# Payload.net
KiCad netlist of a schematic drawn in Altium Designer
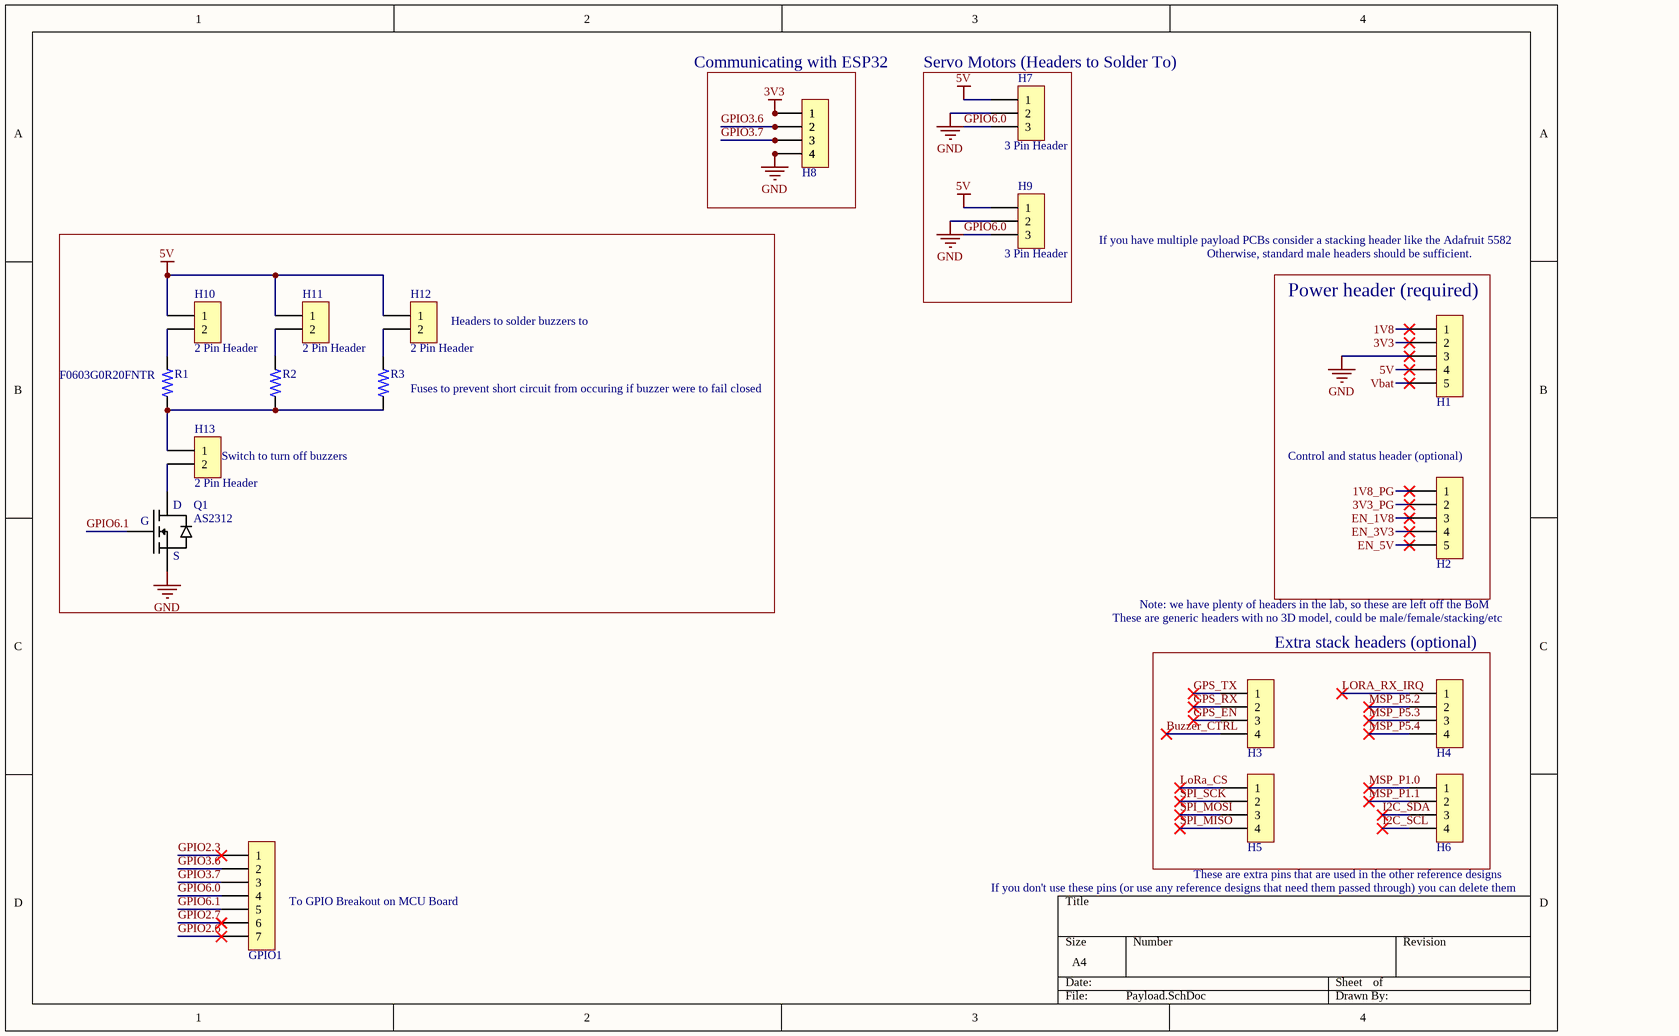
[diagram p0: Payload.SchDoc]

(export (version "E")
  (design (tool "Eeschema 10.0.6"))
  (components
    (comp (ref "GPIO1")
      (value "HDR,2.54mm,1x7")
      (footprint "APSS Connectors:HEADER_2.54MM_1x7PIN")
      (description "Connector - 2.54mm, 1x7-pin")
      (libsource (lib "APSS Connectors") (part "HDR,2.54mm,1x7"))
    )
    (comp (ref "H1")
      (value "Header - 2.54mm,1x5-pin")
      (footprint "HEADER_2.54MM_1x5PIN")
      (libsource (lib "APSS Generic Components") (part "Header - 2.54mm,1x5-pin"))
    )
    (comp (ref "H2")
      (value "Header - 2.54mm,1x5-pin")
      (footprint "HEADER_2.54MM_1x5PIN")
      (libsource (lib "APSS Generic Components") (part "Header - 2.54mm,1x5-pin"))
    )
    (comp (ref "H3")
      (value "Header - 2.54mm,1x4-pin")
      (footprint "HEADER_2.54MM_1x4PIN")
      (libsource (lib "APSS Generic Components") (part "Header - 2.54mm,1x4-pin"))
    )
    (comp (ref "H4")
      (value "Header - 2.54mm,1x4-pin")
      (footprint "HEADER_2.54MM_1x4PIN")
      (libsource (lib "APSS Generic Components") (part "Header - 2.54mm,1x4-pin"))
    )
    (comp (ref "H5")
      (value "Header - 2.54mm,1x4-pin")
      (footprint "HEADER_2.54MM_1x4PIN")
      (libsource (lib "APSS Generic Components") (part "Header - 2.54mm,1x4-pin"))
    )
    (comp (ref "H6")
      (value "Header - 2.54mm,1x4-pin")
      (footprint "HEADER_2.54MM_1x4PIN")
      (libsource (lib "APSS Generic Components") (part "Header - 2.54mm,1x4-pin"))
    )
    (comp (ref "H7")
      (value "3 Pin Header")
      (footprint "3 Pin Header")
      (libsource (lib "Different Header Pin Numbers") (part "3 Pin Header"))
    )
    (comp (ref "H8")
      (value "Header - 2.54mm,1x4-pin")
      (footprint "HEADER_2.54MM_1x4PIN")
      (libsource (lib "APSS Generic Components") (part "Header - 2.54mm,1x4-pin"))
    )
    (comp (ref "H9")
      (value "3 Pin Header")
      (footprint "3 Pin Header")
      (libsource (lib "Different Header Pin Numbers") (part "3 Pin Header"))
    )
    (comp (ref "H10")
      (value "2 Pin Header")
      (footprint "2 Pin Header")
      (libsource (lib "Different Header Pin Numbers") (part "2 Pin Header"))
    )
    (comp (ref "H11")
      (value "2 Pin Header")
      (footprint "2 Pin Header")
      (libsource (lib "Different Header Pin Numbers") (part "2 Pin Header"))
    )
    (comp (ref "H12")
      (value "2 Pin Header")
      (footprint "2 Pin Header")
      (libsource (lib "Different Header Pin Numbers") (part "2 Pin Header"))
    )
    (comp (ref "H13")
      (value "2 Pin Header")
      (footprint "2 Pin Header")
      (libsource (lib "Different Header Pin Numbers") (part "2 Pin Header"))
    )
    (comp (ref "Q1")
      (value "AS2312")
      (footprint "APSS Prototype Parts:SOT23-3N-1.15mm")
      (description "Transistor - MOSFET, N-Channel AS2312")
      (fields (field (name "POWER") "1.2W") (field (name "APSS STANDARD PART") "APSS Standard"))
      (libsource (lib "APSS Prototype Parts") (part "AS2312"))
    )
    (comp (ref "R1")
      (value "F0603G0R20FNTR")
      (footprint "CAPC1608X90")
      (description "200 mA AC 32 V DC Fuse Board Mount (Cartridge Style Excluded) Surface Mount 0603 (1608 Metric)")
      (fields (field (name "MF") "AVX"))
      (libsource (lib "F0603G0R20FNTR") (part "F0603G0R20FNTR"))
    )
    (comp (ref "R2")
      (value "F0603G0R20FNTR")
      (footprint "CAPC1608X90")
      (description "200 mA AC 32 V DC Fuse Board Mount (Cartridge Style Excluded) Surface Mount 0603 (1608 Metric)")
      (fields (field (name "MF") "AVX"))
      (libsource (lib "F0603G0R20FNTR") (part "F0603G0R20FNTR"))
    )
    (comp (ref "R3")
      (value "F0603G0R20FNTR")
      (footprint "CAPC1608X90")
      (description "200 mA AC 32 V DC Fuse Board Mount (Cartridge Style Excluded) Surface Mount 0603 (1608 Metric)")
      (fields (field (name "MF") "AVX"))
      (libsource (lib "F0603G0R20FNTR") (part "F0603G0R20FNTR"))
    )
  )
  (nets
    (net (code "1") (name "/1V8") (class "Default")
      (node (ref "H1") (pin "1") (pinfunction "1_1") (pintype "passive+no_connect"))
    )
    (net (code "2") (name "/1V8_PG") (class "Default")
      (node (ref "H2") (pin "1") (pinfunction "1_1") (pintype "passive+no_connect"))
    )
    (net (code "3") (name "/3V3_PG") (class "Default")
      (node (ref "H2") (pin "2") (pinfunction "2_2") (pintype "passive+no_connect"))
    )
    (net (code "4") (name "/Buzzer_CTRL") (class "Default")
      (node (ref "H3") (pin "4") (pinfunction "4_4") (pintype "passive+no_connect"))
    )
    (net (code "5") (name "/EN_1V8") (class "Default")
      (node (ref "H2") (pin "3") (pinfunction "3_3") (pintype "passive+no_connect"))
    )
    (net (code "6") (name "/EN_3V3") (class "Default")
      (node (ref "H2") (pin "4") (pinfunction "4_4") (pintype "passive+no_connect"))
    )
    (net (code "7") (name "/EN_5V") (class "Default")
      (node (ref "H2") (pin "5") (pinfunction "5_5") (pintype "passive+no_connect"))
    )
    (net (code "8") (name "/GPIO2.3") (class "Default")
      (node (ref "GPIO1") (pin "1") (pinfunction "1_1") (pintype "passive+no_connect"))
    )
    (net (code "9") (name "/GPIO2.6") (class "Default")
      (node (ref "GPIO1") (pin "7") (pinfunction "7_7") (pintype "passive+no_connect"))
    )
    (net (code "10") (name "/GPIO2.7") (class "Default")
      (node (ref "GPIO1") (pin "6") (pinfunction "6_6") (pintype "passive+no_connect"))
    )
    (net (code "11") (name "/GPIO3.6") (class "Default")
      (node (ref "GPIO1") (pin "2") (pinfunction "2_2") (pintype "passive"))
      (node (ref "H8") (pin "2") (pinfunction "2_2") (pintype "passive"))
    )
    (net (code "12") (name "/GPIO3.7") (class "Default")
      (node (ref "GPIO1") (pin "3") (pinfunction "3_3") (pintype "passive"))
      (node (ref "H8") (pin "3") (pinfunction "3_3") (pintype "passive"))
    )
    (net (code "13") (name "/GPIO6.0") (class "Default")
      (node (ref "GPIO1") (pin "4") (pinfunction "4_4") (pintype "passive"))
      (node (ref "H7") (pin "3") (pinfunction "3_3") (pintype "passive"))
      (node (ref "H9") (pin "3") (pinfunction "3_3") (pintype "passive"))
    )
    (net (code "14") (name "/GPIO6.1") (class "Default")
      (node (ref "GPIO1") (pin "5") (pinfunction "5_5") (pintype "passive"))
      (node (ref "Q1") (pin "1") (pinfunction "G_1") (pintype "passive"))
    )
    (net (code "15") (name "/GPS_EN") (class "Default")
      (node (ref "H3") (pin "3") (pinfunction "3_3") (pintype "passive+no_connect"))
    )
    (net (code "16") (name "/GPS_RX") (class "Default")
      (node (ref "H3") (pin "2") (pinfunction "2_2") (pintype "passive+no_connect"))
    )
    (net (code "17") (name "/GPS_TX") (class "Default")
      (node (ref "H3") (pin "1") (pinfunction "1_1") (pintype "passive+no_connect"))
    )
    (net (code "18") (name "/I2C_SCL") (class "Default")
      (node (ref "H6") (pin "4") (pinfunction "4_4") (pintype "passive+no_connect"))
    )
    (net (code "19") (name "/I2C_SDA") (class "Default")
      (node (ref "H6") (pin "3") (pinfunction "3_3") (pintype "passive+no_connect"))
    )
    (net (code "20") (name "/LORA_RX_IRQ") (class "Default")
      (node (ref "H4") (pin "1") (pinfunction "1_1") (pintype "passive+no_connect"))
    )
    (net (code "21") (name "/LoRa_CS") (class "Default")
      (node (ref "H5") (pin "1") (pinfunction "1_1") (pintype "passive+no_connect"))
    )
    (net (code "22") (name "/MSP_P1.0") (class "Default")
      (node (ref "H6") (pin "1") (pinfunction "1_1") (pintype "passive+no_connect"))
    )
    (net (code "23") (name "/MSP_P1.1") (class "Default")
      (node (ref "H6") (pin "2") (pinfunction "2_2") (pintype "passive+no_connect"))
    )
    (net (code "24") (name "/MSP_P5.2") (class "Default")
      (node (ref "H4") (pin "2") (pinfunction "2_2") (pintype "passive+no_connect"))
    )
    (net (code "25") (name "/MSP_P5.3") (class "Default")
      (node (ref "H4") (pin "3") (pinfunction "3_3") (pintype "passive+no_connect"))
    )
    (net (code "26") (name "/MSP_P5.4") (class "Default")
      (node (ref "H4") (pin "4") (pinfunction "4_4") (pintype "passive+no_connect"))
    )
    (net (code "27") (name "/SPI_MISO") (class "Default")
      (node (ref "H5") (pin "4") (pinfunction "4_4") (pintype "passive+no_connect"))
    )
    (net (code "28") (name "/SPI_MOSI") (class "Default")
      (node (ref "H5") (pin "3") (pinfunction "3_3") (pintype "passive+no_connect"))
    )
    (net (code "29") (name "/SPI_SCK") (class "Default")
      (node (ref "H5") (pin "2") (pinfunction "2_2") (pintype "passive+no_connect"))
    )
    (net (code "30") (name "/Vbat") (class "Default")
      (node (ref "H1") (pin "5") (pinfunction "5_5") (pintype "passive+no_connect"))
    )
    (net (code "31") (name "3V3") (class "Default")
      (node (ref "H1") (pin "2") (pinfunction "2_2") (pintype "passive"))
      (node (ref "H8") (pin "1") (pinfunction "1_1") (pintype "passive"))
    )
    (net (code "32") (name "5V") (class "Default")
      (node (ref "H1") (pin "4") (pinfunction "4_4") (pintype "passive"))
      (node (ref "H10") (pin "1") (pinfunction "1_1") (pintype "passive"))
      (node (ref "H11") (pin "1") (pinfunction "1_1") (pintype "passive"))
      (node (ref "H12") (pin "1") (pinfunction "1_1") (pintype "passive"))
      (node (ref "H7") (pin "1") (pinfunction "1_1") (pintype "passive"))
      (node (ref "H9") (pin "1") (pinfunction "1_1") (pintype "passive"))
    )
    (net (code "33") (name "GND") (class "Default")
      (node (ref "H1") (pin "3") (pinfunction "3_3") (pintype "passive"))
      (node (ref "H7") (pin "2") (pinfunction "2_2") (pintype "passive"))
      (node (ref "H8") (pin "4") (pinfunction "4_4") (pintype "passive"))
      (node (ref "H9") (pin "2") (pinfunction "2_2") (pintype "passive"))
      (node (ref "Q1") (pin "2") (pinfunction "S_2") (pintype "passive"))
    )
    (net (code "34") (name "Net-(H10-Pad2)") (class "Default")
      (node (ref "H10") (pin "2") (pinfunction "2_2") (pintype "passive"))
      (node (ref "R1") (pin "2") (pinfunction "2_2") (pintype "passive"))
    )
    (net (code "35") (name "Net-(H11-Pad2)") (class "Default")
      (node (ref "H11") (pin "2") (pinfunction "2_2") (pintype "passive"))
      (node (ref "R2") (pin "2") (pinfunction "2_2") (pintype "passive"))
    )
    (net (code "36") (name "Net-(H12-Pad2)") (class "Default")
      (node (ref "H12") (pin "2") (pinfunction "2_2") (pintype "passive"))
      (node (ref "R3") (pin "2") (pinfunction "2_2") (pintype "passive"))
    )
    (net (code "37") (name "Net-(H13-Pad1)") (class "Default")
      (node (ref "H13") (pin "1") (pinfunction "1_1") (pintype "passive"))
      (node (ref "R1") (pin "1") (pinfunction "1_1") (pintype "passive"))
      (node (ref "R2") (pin "1") (pinfunction "1_1") (pintype "passive"))
      (node (ref "R3") (pin "1") (pinfunction "1_1") (pintype "passive"))
    )
    (net (code "38") (name "Net-(Q1-D)") (class "Default")
      (node (ref "H13") (pin "2") (pinfunction "2_2") (pintype "passive"))
      (node (ref "Q1") (pin "3") (pinfunction "D_3") (pintype "passive"))
    )
  )
)
